# kaga_iot.net
KiCad netlist of a schematic drawn in EAGLE
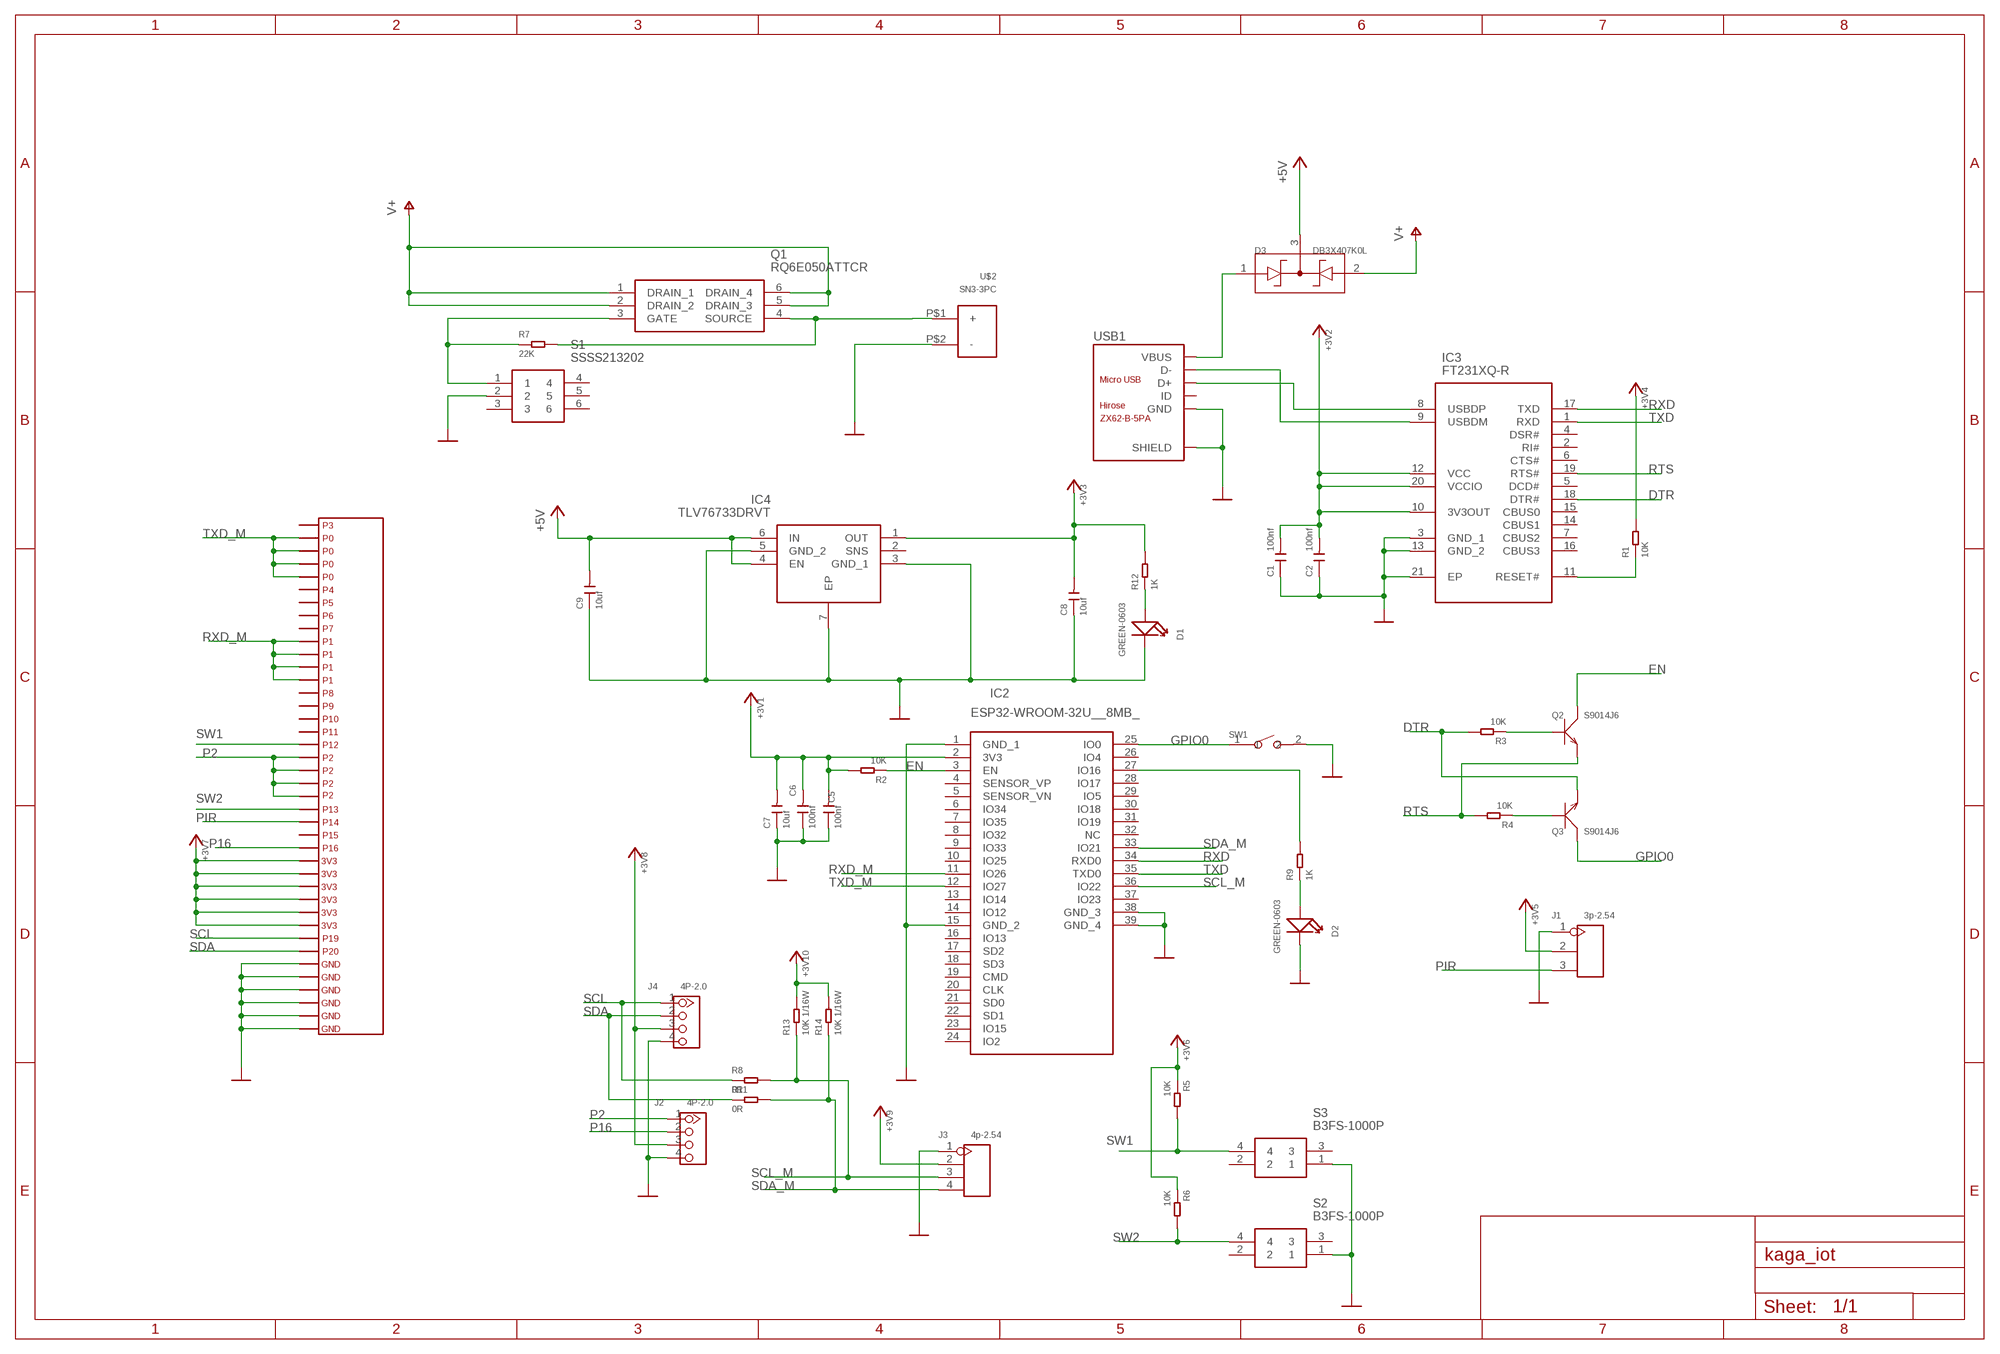
[diagram p0: schematic, sheet 1]

(export (version "E")
  (design (tool "Eeschema 10.0.6"))
  (components
    (comp (ref "C1")
      (value "100nf")
      (footprint "eagle-import:C0603")
      (fields (field (name "MPN") "CC0603KRX7R9BB104"))
      (libsource (lib "eagle-import") (part "CERAMIC-100NF-50V-10%-X7R(0603)"))
    )
    (comp (ref "C2")
      (value "100nf")
      (footprint "eagle-import:C0603")
      (fields (field (name "MPN") "CC0603KRX7R9BB104"))
      (libsource (lib "eagle-import") (part "CERAMIC-100NF-50V-10%-X7R(0603)"))
    )
    (comp (ref "C5")
      (value "100nf")
      (footprint "eagle-import:C0603")
      (fields (field (name "MPN") "CC0603KRX7R9BB104"))
      (libsource (lib "eagle-import") (part "CERAMIC-100NF-50V-10%-X7R(0603)"))
    )
    (comp (ref "C6")
      (value "100nf")
      (footprint "eagle-import:C0603")
      (fields (field (name "MPN") "CC0603KRX7R9BB104"))
      (libsource (lib "eagle-import") (part "CERAMIC-100NF-50V-10%-X7R(0603)"))
    )
    (comp (ref "C7")
      (value "10uf")
      (footprint "eagle-import:C0603")
      (fields (field (name "MPN") "CC0603KRX5R6BB106"))
      (libsource (lib "eagle-import") (part "Seeed-OPL-Capacitor_CERAMIC-10UF-10V-10%-X5R(0603)"))
    )
    (comp (ref "C8")
      (value "10uf")
      (footprint "eagle-import:C0603")
      (fields (field (name "MPN") "CC0603KRX5R6BB106"))
      (libsource (lib "eagle-import") (part "CERAMIC-10UF-10V-10%-X5R(0603)"))
    )
    (comp (ref "C9")
      (value "10uf")
      (footprint "eagle-import:C0603")
      (fields (field (name "MPN") "CC0603KRX5R6BB106"))
      (libsource (lib "eagle-import") (part "CERAMIC-10UF-10V-10%-X5R(0603)"))
    )
    (comp (ref "D1")
      (value "GREEN-0603")
      (footprint "eagle-import:LED-0603")
      (fields (field (name "MPN") "19-217-G7C-AN1P2-3T"))
      (libsource (lib "eagle-import") (part "SMD-LED-CLEAR-GREEN(0603)"))
    )
    (comp (ref "D2")
      (value "GREEN-0603")
      (footprint "eagle-import:LED-0603")
      (fields (field (name "MPN") "19-217-G7C-AN1P2-3T"))
      (libsource (lib "eagle-import") (part "SMD-LED-CLEAR-GREEN(0603)"))
    )
    (comp (ref "D3")
      (value "DB3X407K0L")
      (footprint "eagle-import:SOT-23")
      (fields (field (name "MPN") "BAT54C-215"))
      (libsource (lib "eagle-import") (part "SMD-DIODE-SCHOTTKY-30V-200MA(SOT-23)"))
    )
    (comp (ref "IC2")
      (value "ESP32-WROOM-32U__8MB_")
      (footprint "eagle-import:ESP32WROOM32U8MB")
      (fields (field (name "MANUFACTURER_PART_NUMBER") "ESP32-WROOM-32U (8MB)"))
      (libsource (lib "eagle-import") (part "ESP32-WROOM-32U__8MB_"))
    )
    (comp (ref "IC3")
      (value "FT231XQ-R")
      (footprint "eagle-import:QFN50P400X400X80-21N")
      (fields (field (name "RS_PART_NUMBER") "7570045P"))
      (libsource (lib "eagle-import") (part "FT231XQ-R"))
    )
    (comp (ref "IC4")
      (value "TLV76733DRVT")
      (footprint "eagle-import:SON65P200X200X80-7N")
      (libsource (lib "eagle-import") (part "TLV76733DRVT"))
    )
    (comp (ref "J1")
      (value "3p-2.54")
      (footprint "eagle-import:H3-2.54")
      (fields (field (name "MPN") "F185-1103A0BSYA1"))
      (libsource (lib "eagle-import") (part "DIP-BLACK-FEMALE-HEADER-VERT(3P-2.54)"))
    )
    (comp (ref "J2")
      (value "4P-2.0")
      (footprint "eagle-import:HW4-2.0")
      (libsource (lib "eagle-import") (part "GROVE-CONNECTOR-DIP(4P-2.0)"))
    )
    (comp (ref "J3")
      (value "4p-2.54")
      (footprint "eagle-import:H4-2.54")
      (fields (field (name "MPN") "F185-1104A1BSYA1"))
      (libsource (lib "eagle-import") (part "DIP-BLACK-FEMALE-HEADER-VERT(4P-2.54)"))
    )
    (comp (ref "J4")
      (value "4P-2.0")
      (footprint "eagle-import:HW4-2.0")
      (libsource (lib "eagle-import") (part "GROVE-CONNECTOR-DIP(4P-2.0)"))
    )
    (comp (ref "Q1")
      (value "RQ6E050ATTCR")
      (footprint "eagle-import:SOT95P280X100-6N")
      (fields (field (name "RS_PART_NUMBER") "1246805P"))
      (libsource (lib "eagle-import") (part "RQ6E050ATTCR"))
    )
    (comp (ref "Q2")
      (value "S9014J6")
      (footprint "eagle-import:SOT-23")
      (libsource (lib "eagle-import") (part "SMD-TRANSISTOR-NPN-50V-100MA-S9014J6(SOT-23)"))
    )
    (comp (ref "Q3")
      (value "S9014J6")
      (footprint "eagle-import:SOT-23")
      (libsource (lib "eagle-import") (part "SMD-TRANSISTOR-NPN-50V-100MA-S9014J6(SOT-23)"))
    )
    (comp (ref "R1")
      (value "10K")
      (footprint "eagle-import:R0603")
      (fields (field (name "MPN") "RC0603FR-0710KL"))
      (libsource (lib "eagle-import") (part "SMD-RES-10K-1%-1/10W(0603)"))
    )
    (comp (ref "R2")
      (value "10K")
      (footprint "eagle-import:R0603")
      (fields (field (name "MPN") "RC0603FR-0710KL"))
      (libsource (lib "eagle-import") (part "SMD-RES-10K-1%-1/10W(0603)"))
    )
    (comp (ref "R3")
      (value "10K")
      (footprint "eagle-import:R0603")
      (fields (field (name "MPN") "RC0603FR-0710KL"))
      (libsource (lib "eagle-import") (part "SMD-RES-10K-1%-1/10W(0603)"))
    )
    (comp (ref "R4")
      (value "10K")
      (footprint "eagle-import:R0603")
      (fields (field (name "MPN") "RC0603FR-0710KL"))
      (libsource (lib "eagle-import") (part "SMD-RES-10K-1%-1/10W(0603)"))
    )
    (comp (ref "R5")
      (value "10K")
      (footprint "eagle-import:R0603")
      (fields (field (name "MPN") "RC0603FR-0710KL"))
      (libsource (lib "eagle-import") (part "SMD-RES-10K-1%-1/10W(0603)"))
    )
    (comp (ref "R6")
      (value "10K")
      (footprint "eagle-import:R0603")
      (fields (field (name "MPN") "RC0603FR-0710KL"))
      (libsource (lib "eagle-import") (part "SMD-RES-10K-1%-1/10W(0603)"))
    )
    (comp (ref "R7")
      (value "22K")
      (footprint "eagle-import:R0402")
      (fields (field (name "MPN") "RC0402FR-0722KL"))
      (libsource (lib "eagle-import") (part "SMD-RES-22K-1%-1/16W(0402)"))
    )
    (comp (ref "R8")
      (value "0R")
      (footprint "eagle-import:R0402")
      (fields (field (name "MPN") "RC0402JR-070RL"))
      (libsource (lib "eagle-import") (part "SMD-RES-0R-5%-1/16W(0402)"))
    )
    (comp (ref "R9")
      (value "1K")
      (footprint "eagle-import:R0603")
      (fields (field (name "MPN") "RC0603FR-071KL"))
      (libsource (lib "eagle-import") (part "SMD-RES-1K-1%-1/10W(0603)"))
    )
    (comp (ref "R11")
      (value "0R")
      (footprint "eagle-import:R0402")
      (fields (field (name "MPN") "RC0402JR-070RL"))
      (libsource (lib "eagle-import") (part "SMD-RES-0R-5%-1/16W(0402)"))
    )
    (comp (ref "R12")
      (value "1K")
      (footprint "eagle-import:R0603")
      (fields (field (name "MPN") "RC0603FR-071KL"))
      (libsource (lib "eagle-import") (part "SMD-RES-1K-1%-1/10W(0603)"))
    )
    (comp (ref "R13")
      (value "10K 1/16W")
      (footprint "eagle-import:R0402")
      (fields (field (name "MPN") "RC0402FR-0710KL"))
      (libsource (lib "eagle-import") (part "SMD-RES-10K-1%-1/16W(0402)"))
    )
    (comp (ref "R14")
      (value "10K 1/16W")
      (footprint "eagle-import:R0402")
      (fields (field (name "MPN") "RC0402FR-0710KL"))
      (libsource (lib "eagle-import") (part "SMD-RES-10K-1%-1/16W(0402)"))
    )
    (comp (ref "S1")
      (value "SSSS213202")
      (footprint "eagle-import:SSSS213202")
      (fields (field (name "RS_PART_NUMBER") "1238917"))
      (libsource (lib "eagle-import") (part "SSSS213202"))
    )
    (comp (ref "S2")
      (value "B3FS-1000P")
      (footprint "eagle-import:B3FS-1000P")
      (fields (field (name "RS_PART_NUMBER") "6821254P"))
      (libsource (lib "eagle-import") (part "B3FS-1000P"))
    )
    (comp (ref "S3")
      (value "B3FS-1000P")
      (footprint "eagle-import:B3FS-1000P")
      (fields (field (name "RS_PART_NUMBER") "6821254P"))
      (libsource (lib "eagle-import") (part "B3FS-1000P"))
    )
    (comp (ref "SW1")
      (value "SMD-BUTTON(2P-3.0X2.5X1.2+0.4MM)-B3U-1000P-2P-SMD")
      (footprint "eagle-import:SW2-2.6-3.0X2.5X1.2+0.4MM")
      (libsource (lib "eagle-import") (part "SMD-BUTTON(2P-3.0X2.5X1.2+0.4MM)-B3U-1000P-2P-SMD"))
    )
    (comp (ref "U$1")
      (value "SMD_BBC_EDG2")
      (footprint "eagle-import:SMD_BBC_EDG2")
      (libsource (lib "eagle-import") (part "SMD_BBC_EDG2"))
    )
    (comp (ref "U$2")
      (value "SN3-3PC")
      (footprint "eagle-import:SN3-3PC")
      (libsource (lib "eagle-import") (part "SN3-3PC"))
    )
    (comp (ref "USB1")
      (value "ZX62-B-5PA")
      (footprint "eagle-import:MICRO-USB5+6P-SMD-0.65-AB")
      (libsource (lib "eagle-import") (part "MICRO-USB-SMD(ZX62-B-5PA)"))
    )
  )
  (nets
    (net (code "1") (name "+5V") (class "Default")
      (node (ref "C9") (pin "2") (pinfunction "2_2") (pintype "passive"))
      (node (ref "D3") (pin "3") (pinfunction "3_3") (pintype "bidirectional"))
      (node (ref "IC4") (pin "4") (pinfunction "EN_4") (pintype "bidirectional"))
      (node (ref "IC4") (pin "6") (pinfunction "IN_6") (pintype "bidirectional"))
    )
    (net (code "2") (name "/DTR") (class "Default")
      (node (ref "IC3") (pin "18") (pinfunction "DTR#_18") (pintype "bidirectional"))
      (node (ref "Q3") (pin "2") (pinfunction "E_2") (pintype "passive"))
      (node (ref "R3") (pin "2") (pinfunction "2_2") (pintype "passive"))
    )
    (net (code "3") (name "/EN") (class "Default")
      (node (ref "IC2") (pin "3") (pinfunction "EN_3") (pintype "bidirectional"))
      (node (ref "Q2") (pin "3") (pinfunction "C_3") (pintype "passive"))
      (node (ref "R2") (pin "1") (pinfunction "1_1") (pintype "passive"))
    )
    (net (code "4") (name "/GPIO0") (class "Default")
      (node (ref "IC2") (pin "25") (pinfunction "IO0_25") (pintype "bidirectional"))
      (node (ref "Q3") (pin "3") (pinfunction "C_3") (pintype "passive"))
      (node (ref "SW1") (pin "1") (pinfunction "1_1") (pintype "bidirectional"))
    )
    (net (code "5") (name "/P2") (class "Default")
      (node (ref "J2") (pin "1") (pinfunction "1_1") (pintype "bidirectional"))
      (node (ref "U$1") (pin "P$59") (pinfunction "P$59_P$59") (pintype "bidirectional"))
      (node (ref "U$1") (pin "P$60") (pinfunction "P$60_P$60") (pintype "bidirectional"))
      (node (ref "U$1") (pin "P$61") (pinfunction "P$61_P$61") (pintype "bidirectional"))
      (node (ref "U$1") (pin "P$62") (pinfunction "P$62_P$62") (pintype "bidirectional"))
    )
    (net (code "6") (name "/P16") (class "Default")
      (node (ref "J2") (pin "2") (pinfunction "2_2") (pintype "bidirectional"))
      (node (ref "U$1") (pin "P$55") (pinfunction "P$55_P$55") (pintype "bidirectional"))
    )
    (net (code "7") (name "/PIR") (class "Default")
      (node (ref "J1") (pin "3") (pinfunction "P$3_3") (pintype "bidirectional"))
      (node (ref "U$1") (pin "P$57") (pinfunction "P$57_P$57") (pintype "bidirectional"))
    )
    (net (code "8") (name "/RTS") (class "Default")
      (node (ref "IC3") (pin "19") (pinfunction "RTS#_19") (pintype "bidirectional"))
      (node (ref "Q2") (pin "2") (pinfunction "E_2") (pintype "passive"))
      (node (ref "R4") (pin "2") (pinfunction "2_2") (pintype "passive"))
    )
    (net (code "9") (name "/RXD") (class "Default")
      (node (ref "IC2") (pin "34") (pinfunction "RXD0_34") (pintype "bidirectional"))
      (node (ref "IC3") (pin "17") (pinfunction "TXD_17") (pintype "bidirectional"))
    )
    (net (code "10") (name "/RXD_M") (class "Default")
      (node (ref "IC2") (pin "11") (pinfunction "IO26_11") (pintype "bidirectional"))
      (node (ref "U$1") (pin "P$68") (pinfunction "P$68_P$68") (pintype "bidirectional"))
      (node (ref "U$1") (pin "P$69") (pinfunction "P$69_P$69") (pintype "bidirectional"))
      (node (ref "U$1") (pin "P$70") (pinfunction "P$70_P$70") (pintype "bidirectional"))
      (node (ref "U$1") (pin "P$71") (pinfunction "P$71_P$71") (pintype "bidirectional"))
    )
    (net (code "11") (name "/SCL") (class "Default")
      (node (ref "J4") (pin "1") (pinfunction "1_1") (pintype "bidirectional"))
      (node (ref "R8") (pin "1") (pinfunction "1_1") (pintype "passive"))
      (node (ref "U$1") (pin "P$48") (pinfunction "P$48_P$48") (pintype "bidirectional"))
    )
    (net (code "12") (name "/SCL_M") (class "Default")
      (node (ref "IC2") (pin "36") (pinfunction "IO22_36") (pintype "bidirectional"))
      (node (ref "J3") (pin "3") (pinfunction "P$3_3") (pintype "bidirectional"))
      (node (ref "R13") (pin "1") (pinfunction "1_1") (pintype "passive"))
      (node (ref "R8") (pin "2") (pinfunction "2_2") (pintype "passive"))
    )
    (net (code "13") (name "/SDA") (class "Default")
      (node (ref "J4") (pin "2") (pinfunction "2_2") (pintype "bidirectional"))
      (node (ref "R11") (pin "1") (pinfunction "1_1") (pintype "passive"))
      (node (ref "U$1") (pin "P$47") (pinfunction "P$47_P$47") (pintype "bidirectional"))
    )
    (net (code "14") (name "/SDA_M") (class "Default")
      (node (ref "IC2") (pin "33") (pinfunction "IO21_33") (pintype "bidirectional"))
      (node (ref "J3") (pin "4") (pinfunction "P$4_4") (pintype "bidirectional"))
      (node (ref "R11") (pin "2") (pinfunction "2_2") (pintype "passive"))
      (node (ref "R14") (pin "1") (pinfunction "1_1") (pintype "passive"))
    )
    (net (code "15") (name "/SW1") (class "Default")
      (node (ref "R5") (pin "2") (pinfunction "2_2") (pintype "passive"))
      (node (ref "S3") (pin "4") (pinfunction "4_4") (pintype "bidirectional"))
      (node (ref "U$1") (pin "P$63") (pinfunction "P$63_P$63") (pintype "bidirectional"))
    )
    (net (code "16") (name "/SW2") (class "Default")
      (node (ref "R6") (pin "2") (pinfunction "2_2") (pintype "passive"))
      (node (ref "S2") (pin "4") (pinfunction "4_4") (pintype "bidirectional"))
      (node (ref "U$1") (pin "P$58") (pinfunction "P$58_P$58") (pintype "bidirectional"))
    )
    (net (code "17") (name "/TXD") (class "Default")
      (node (ref "IC2") (pin "35") (pinfunction "TXD0_35") (pintype "bidirectional"))
      (node (ref "IC3") (pin "1") (pinfunction "RXD_1") (pintype "bidirectional"))
    )
    (net (code "18") (name "/TXD_M") (class "Default")
      (node (ref "IC2") (pin "12") (pinfunction "IO27_12") (pintype "bidirectional"))
      (node (ref "U$1") (pin "P$76") (pinfunction "P$76_P$76") (pintype "bidirectional"))
      (node (ref "U$1") (pin "P$77") (pinfunction "P$77_P$77") (pintype "bidirectional"))
      (node (ref "U$1") (pin "P$78") (pinfunction "P$78_P$78") (pintype "bidirectional"))
      (node (ref "U$1") (pin "P$79") (pinfunction "P$79_P$79") (pintype "bidirectional"))
    )
    (net (code "19") (name "Net-(D1-Pad+)") (class "Default")
      (node (ref "D1") (pin "+") (pinfunction "+_+") (pintype "passive"))
      (node (ref "R12") (pin "1") (pinfunction "1_1") (pintype "passive"))
    )
    (net (code "20") (name "Net-(D2-Pad+)") (class "Default")
      (node (ref "D2") (pin "+") (pinfunction "+_+") (pintype "passive"))
      (node (ref "R9") (pin "1") (pinfunction "1_1") (pintype "passive"))
    )
    (net (code "21") (name "Net-(IC2-IO16)") (class "Default")
      (node (ref "IC2") (pin "27") (pinfunction "IO16_27") (pintype "bidirectional"))
      (node (ref "R9") (pin "2") (pinfunction "2_2") (pintype "passive"))
    )
    (net (code "22") (name "Net-(IC3-RESET#)") (class "Default")
      (node (ref "IC3") (pin "11") (pinfunction "RESET#_11") (pintype "bidirectional"))
      (node (ref "R1") (pin "1") (pinfunction "1_1") (pintype "passive"))
    )
    (net (code "23") (name "Net-(IC3-USBDM)") (class "Default")
      (node (ref "IC3") (pin "9") (pinfunction "USBDM_9") (pintype "bidirectional"))
      (node (ref "USB1") (pin "2") (pinfunction "D-_2") (pintype "bidirectional"))
    )
    (net (code "24") (name "Net-(IC3-USBDP)") (class "Default")
      (node (ref "IC3") (pin "8") (pinfunction "USBDP_8") (pintype "bidirectional"))
      (node (ref "USB1") (pin "3") (pinfunction "D+_3") (pintype "bidirectional"))
    )
    (net (code "25") (name "Net-(Q1-GATE)") (class "Default")
      (node (ref "Q1") (pin "3") (pinfunction "GATE_3") (pintype "bidirectional"))
      (node (ref "R7") (pin "1") (pinfunction "1_1") (pintype "passive"))
      (node (ref "S1") (pin "1") (pinfunction "1_1") (pintype "bidirectional"))
    )
    (net (code "26") (name "Net-(Q1-SOURCE)") (class "Default")
      (node (ref "Q1") (pin "4") (pinfunction "SOURCE_4") (pintype "bidirectional"))
      (node (ref "R7") (pin "2") (pinfunction "2_2") (pintype "passive"))
      (node (ref "U$2") (pin "P$1") (pinfunction "+_P$1") (pintype "bidirectional"))
    )
    (net (code "27") (name "Net-(Q2-B)") (class "Default")
      (node (ref "Q2") (pin "1") (pinfunction "B_1") (pintype "passive"))
      (node (ref "R3") (pin "1") (pinfunction "1_1") (pintype "passive"))
    )
    (net (code "28") (name "Net-(Q3-B)") (class "Default")
      (node (ref "Q3") (pin "1") (pinfunction "B_1") (pintype "passive"))
      (node (ref "R4") (pin "1") (pinfunction "1_1") (pintype "passive"))
    )
    (net (code "29") (name "Net-(USB1-VBUS)") (class "Default")
      (node (ref "D3") (pin "1") (pinfunction "1_1") (pintype "bidirectional"))
      (node (ref "USB1") (pin "1") (pinfunction "VBUS_1") (pintype "power_in"))
    )
    (net (code "30") (name "POW_+3V3") (class "Default")
      (node (ref "C1") (pin "2") (pinfunction "2_2") (pintype "passive"))
      (node (ref "C2") (pin "2") (pinfunction "2_2") (pintype "passive"))
      (node (ref "C5") (pin "2") (pinfunction "2_2") (pintype "passive"))
      (node (ref "C6") (pin "2") (pinfunction "2_2") (pintype "passive"))
      (node (ref "C7") (pin "2") (pinfunction "2_2") (pintype "passive"))
      (node (ref "C8") (pin "2") (pinfunction "2_2") (pintype "passive"))
      (node (ref "IC2") (pin "2") (pinfunction "3V3_2") (pintype "bidirectional"))
      (node (ref "IC3") (pin "10") (pinfunction "3V3OUT_10") (pintype "bidirectional"))
      (node (ref "IC3") (pin "12") (pinfunction "VCC_12") (pintype "bidirectional"))
      (node (ref "IC3") (pin "20") (pinfunction "VCCIO_20") (pintype "bidirectional"))
      (node (ref "IC4") (pin "1") (pinfunction "OUT_1") (pintype "bidirectional"))
      (node (ref "J1") (pin "2") (pinfunction "P$2_2") (pintype "bidirectional"))
      (node (ref "J2") (pin "3") (pinfunction "3_3") (pintype "bidirectional"))
      (node (ref "J3") (pin "2") (pinfunction "P$2_2") (pintype "bidirectional"))
      (node (ref "J4") (pin "3") (pinfunction "3_3") (pintype "bidirectional"))
      (node (ref "R1") (pin "2") (pinfunction "2_2") (pintype "passive"))
      (node (ref "R12") (pin "2") (pinfunction "2_2") (pintype "passive"))
      (node (ref "R13") (pin "2") (pinfunction "2_2") (pintype "passive"))
      (node (ref "R14") (pin "2") (pinfunction "2_2") (pintype "passive"))
      (node (ref "R2") (pin "2") (pinfunction "2_2") (pintype "passive"))
      (node (ref "R5") (pin "1") (pinfunction "1_1") (pintype "passive"))
      (node (ref "R6") (pin "1") (pinfunction "1_1") (pintype "passive"))
      (node (ref "U$1") (pin "P$49") (pinfunction "P$49_P$49") (pintype "bidirectional"))
      (node (ref "U$1") (pin "P$50") (pinfunction "P$50_P$50") (pintype "bidirectional"))
      (node (ref "U$1") (pin "P$51") (pinfunction "P$51_P$51") (pintype "bidirectional"))
      (node (ref "U$1") (pin "P$52") (pinfunction "P$52_P$52") (pintype "bidirectional"))
      (node (ref "U$1") (pin "P$53") (pinfunction "P$53_P$53") (pintype "bidirectional"))
      (node (ref "U$1") (pin "P$54") (pinfunction "P$54_P$54") (pintype "bidirectional"))
    )
    (net (code "31") (name "POW_GND") (class "Default")
      (node (ref "C1") (pin "1") (pinfunction "1_1") (pintype "passive"))
      (node (ref "C2") (pin "1") (pinfunction "1_1") (pintype "passive"))
      (node (ref "C5") (pin "1") (pinfunction "1_1") (pintype "passive"))
      (node (ref "C6") (pin "1") (pinfunction "1_1") (pintype "passive"))
      (node (ref "C7") (pin "1") (pinfunction "1_1") (pintype "passive"))
      (node (ref "C8") (pin "1") (pinfunction "1_1") (pintype "passive"))
      (node (ref "C9") (pin "1") (pinfunction "1_1") (pintype "passive"))
      (node (ref "D1") (pin "-") (pinfunction "-_-") (pintype "passive"))
      (node (ref "D2") (pin "-") (pinfunction "-_-") (pintype "passive"))
      (node (ref "IC2") (pin "1") (pinfunction "GND_1_1") (pintype "bidirectional"))
      (node (ref "IC2") (pin "15") (pinfunction "GND_2_15") (pintype "bidirectional"))
      (node (ref "IC2") (pin "38") (pinfunction "GND_3_38") (pintype "bidirectional"))
      (node (ref "IC2") (pin "39") (pinfunction "GND_4_39") (pintype "bidirectional"))
      (node (ref "IC3") (pin "13") (pinfunction "GND_2_13") (pintype "bidirectional"))
      (node (ref "IC3") (pin "21") (pinfunction "EP_21") (pintype "bidirectional"))
      (node (ref "IC3") (pin "3") (pinfunction "GND_1_3") (pintype "bidirectional"))
      (node (ref "IC4") (pin "3") (pinfunction "GND_1_3") (pintype "bidirectional"))
      (node (ref "IC4") (pin "5") (pinfunction "GND_2_5") (pintype "bidirectional"))
      (node (ref "IC4") (pin "7") (pinfunction "EP_7") (pintype "bidirectional"))
      (node (ref "J1") (pin "1") (pinfunction "P$1_1") (pintype "bidirectional"))
      (node (ref "J2") (pin "4") (pinfunction "4_4") (pintype "bidirectional"))
      (node (ref "J3") (pin "1") (pinfunction "P$1_1") (pintype "bidirectional"))
      (node (ref "J4") (pin "4") (pinfunction "4_4") (pintype "bidirectional"))
      (node (ref "S1") (pin "2") (pinfunction "2_2") (pintype "bidirectional"))
      (node (ref "S2") (pin "1") (pinfunction "1_1") (pintype "bidirectional"))
      (node (ref "S3") (pin "1") (pinfunction "1_1") (pintype "bidirectional"))
      (node (ref "SW1") (pin "2") (pinfunction "2_2") (pintype "bidirectional"))
      (node (ref "U$1") (pin "P$41") (pinfunction "P$41_P$41") (pintype "bidirectional"))
      (node (ref "U$1") (pin "P$42") (pinfunction "P$42_P$42") (pintype "bidirectional"))
      (node (ref "U$1") (pin "P$43") (pinfunction "P$43_P$43") (pintype "bidirectional"))
      (node (ref "U$1") (pin "P$44") (pinfunction "P$44_P$44") (pintype "bidirectional"))
      (node (ref "U$1") (pin "P$45") (pinfunction "P$45_P$45") (pintype "bidirectional"))
      (node (ref "U$1") (pin "P$46") (pinfunction "P$46_P$46") (pintype "bidirectional"))
      (node (ref "U$2") (pin "P$2") (pinfunction "-_P$2") (pintype "bidirectional"))
      (node (ref "USB1") (pin "5") (pinfunction "GND_5") (pintype "power_in"))
      (node (ref "USB1") (pin "P1") (pinfunction "SHIELD_P1") (pintype "power_in"))
      (node (ref "USB1") (pin "P2") (pinfunction "SHIELD_P2") (pintype "power_in"))
      (node (ref "USB1") (pin "P3") (pinfunction "SHIELD_P3") (pintype "power_in"))
      (node (ref "USB1") (pin "P4") (pinfunction "SHIELD_P4") (pintype "power_in"))
      (node (ref "USB1") (pin "P5") (pinfunction "SHIELD_P5") (pintype "power_in"))
      (node (ref "USB1") (pin "P6") (pinfunction "SHIELD_P6") (pintype "power_in"))
    )
    (net (code "32") (name "V+") (class "Default")
      (node (ref "D3") (pin "2") (pinfunction "2_2") (pintype "bidirectional"))
      (node (ref "Q1") (pin "1") (pinfunction "DRAIN_1_1") (pintype "bidirectional"))
      (node (ref "Q1") (pin "2") (pinfunction "DRAIN_2_2") (pintype "bidirectional"))
      (node (ref "Q1") (pin "5") (pinfunction "DRAIN_3_5") (pintype "bidirectional"))
      (node (ref "Q1") (pin "6") (pinfunction "DRAIN_4_6") (pintype "bidirectional"))
    )
    (net (code "33") (name "unconnected-(IC2-CLK-Pad20)") (class "Default")
      (node (ref "IC2") (pin "20") (pinfunction "CLK_20") (pintype "bidirectional"))
    )
    (net (code "34") (name "unconnected-(IC2-CMD-Pad19)") (class "Default")
      (node (ref "IC2") (pin "19") (pinfunction "CMD_19") (pintype "bidirectional"))
    )
    (net (code "35") (name "unconnected-(IC2-IO2-Pad24)") (class "Default")
      (node (ref "IC2") (pin "24") (pinfunction "IO2_24") (pintype "bidirectional"))
    )
    (net (code "36") (name "unconnected-(IC2-IO4-Pad26)") (class "Default")
      (node (ref "IC2") (pin "26") (pinfunction "IO4_26") (pintype "bidirectional"))
    )
    (net (code "37") (name "unconnected-(IC2-IO5-Pad29)") (class "Default")
      (node (ref "IC2") (pin "29") (pinfunction "IO5_29") (pintype "bidirectional"))
    )
    (net (code "38") (name "unconnected-(IC2-IO12-Pad14)") (class "Default")
      (node (ref "IC2") (pin "14") (pinfunction "IO12_14") (pintype "bidirectional"))
    )
    (net (code "39") (name "unconnected-(IC2-IO13-Pad16)") (class "Default")
      (node (ref "IC2") (pin "16") (pinfunction "IO13_16") (pintype "bidirectional"))
    )
    (net (code "40") (name "unconnected-(IC2-IO14-Pad13)") (class "Default")
      (node (ref "IC2") (pin "13") (pinfunction "IO14_13") (pintype "bidirectional"))
    )
    (net (code "41") (name "unconnected-(IC2-IO15-Pad23)") (class "Default")
      (node (ref "IC2") (pin "23") (pinfunction "IO15_23") (pintype "bidirectional"))
    )
    (net (code "42") (name "unconnected-(IC2-IO17-Pad28)") (class "Default")
      (node (ref "IC2") (pin "28") (pinfunction "IO17_28") (pintype "bidirectional"))
    )
    (net (code "43") (name "unconnected-(IC2-IO18-Pad30)") (class "Default")
      (node (ref "IC2") (pin "30") (pinfunction "IO18_30") (pintype "bidirectional"))
    )
    (net (code "44") (name "unconnected-(IC2-IO19-Pad31)") (class "Default")
      (node (ref "IC2") (pin "31") (pinfunction "IO19_31") (pintype "bidirectional"))
    )
    (net (code "45") (name "unconnected-(IC2-IO23-Pad37)") (class "Default")
      (node (ref "IC2") (pin "37") (pinfunction "IO23_37") (pintype "bidirectional"))
    )
    (net (code "46") (name "unconnected-(IC2-IO25-Pad10)") (class "Default")
      (node (ref "IC2") (pin "10") (pinfunction "IO25_10") (pintype "bidirectional"))
    )
    (net (code "47") (name "unconnected-(IC2-IO32-Pad8)") (class "Default")
      (node (ref "IC2") (pin "8") (pinfunction "IO32_8") (pintype "bidirectional"))
    )
    (net (code "48") (name "unconnected-(IC2-IO33-Pad9)") (class "Default")
      (node (ref "IC2") (pin "9") (pinfunction "IO33_9") (pintype "bidirectional"))
    )
    (net (code "49") (name "unconnected-(IC2-IO34-Pad6)") (class "Default")
      (node (ref "IC2") (pin "6") (pinfunction "IO34_6") (pintype "bidirectional"))
    )
    (net (code "50") (name "unconnected-(IC2-IO35-Pad7)") (class "Default")
      (node (ref "IC2") (pin "7") (pinfunction "IO35_7") (pintype "bidirectional"))
    )
    (net (code "51") (name "unconnected-(IC2-NC-Pad32)") (class "Default")
      (node (ref "IC2") (pin "32") (pinfunction "NC_32") (pintype "no_connect"))
    )
    (net (code "52") (name "unconnected-(IC2-SD0-Pad21)") (class "Default")
      (node (ref "IC2") (pin "21") (pinfunction "SD0_21") (pintype "bidirectional"))
    )
    (net (code "53") (name "unconnected-(IC2-SD1-Pad22)") (class "Default")
      (node (ref "IC2") (pin "22") (pinfunction "SD1_22") (pintype "bidirectional"))
    )
    (net (code "54") (name "unconnected-(IC2-SD2-Pad17)") (class "Default")
      (node (ref "IC2") (pin "17") (pinfunction "SD2_17") (pintype "bidirectional"))
    )
    (net (code "55") (name "unconnected-(IC2-SD3-Pad18)") (class "Default")
      (node (ref "IC2") (pin "18") (pinfunction "SD3_18") (pintype "bidirectional"))
    )
    (net (code "56") (name "unconnected-(IC2-SENSOR_VN-Pad5)") (class "Default")
      (node (ref "IC2") (pin "5") (pinfunction "SENSOR_VN_5") (pintype "bidirectional"))
    )
    (net (code "57") (name "unconnected-(IC2-SENSOR_VP-Pad4)") (class "Default")
      (node (ref "IC2") (pin "4") (pinfunction "SENSOR_VP_4") (pintype "bidirectional"))
    )
    (net (code "58") (name "unconnected-(IC3-CBUS0-Pad15)") (class "Default")
      (node (ref "IC3") (pin "15") (pinfunction "CBUS0_15") (pintype "bidirectional"))
    )
    (net (code "59") (name "unconnected-(IC3-CBUS1-Pad14)") (class "Default")
      (node (ref "IC3") (pin "14") (pinfunction "CBUS1_14") (pintype "bidirectional"))
    )
    (net (code "60") (name "unconnected-(IC3-CBUS2-Pad7)") (class "Default")
      (node (ref "IC3") (pin "7") (pinfunction "CBUS2_7") (pintype "bidirectional"))
    )
    (net (code "61") (name "unconnected-(IC3-CBUS3-Pad16)") (class "Default")
      (node (ref "IC3") (pin "16") (pinfunction "CBUS3_16") (pintype "bidirectional"))
    )
    (net (code "62") (name "unconnected-(IC3-CTS#-Pad6)") (class "Default")
      (node (ref "IC3") (pin "6") (pinfunction "CTS#_6") (pintype "bidirectional"))
    )
    (net (code "63") (name "unconnected-(IC3-DCD#-Pad5)") (class "Default")
      (node (ref "IC3") (pin "5") (pinfunction "DCD#_5") (pintype "bidirectional"))
    )
    (net (code "64") (name "unconnected-(IC3-DSR#-Pad4)") (class "Default")
      (node (ref "IC3") (pin "4") (pinfunction "DSR#_4") (pintype "bidirectional"))
    )
    (net (code "65") (name "unconnected-(IC3-RI#-Pad2)") (class "Default")
      (node (ref "IC3") (pin "2") (pinfunction "RI#_2") (pintype "bidirectional"))
    )
    (net (code "66") (name "unconnected-(IC4-SNS-Pad2)") (class "Default")
      (node (ref "IC4") (pin "2") (pinfunction "SNS_2") (pintype "bidirectional"))
    )
    (net (code "67") (name "unconnected-(S1-Pad3)") (class "Default")
      (node (ref "S1") (pin "3") (pinfunction "3_3") (pintype "bidirectional"))
    )
    (net (code "68") (name "unconnected-(S1-Pad4)") (class "Default")
      (node (ref "S1") (pin "4") (pinfunction "4_4") (pintype "bidirectional"))
    )
    (net (code "69") (name "unconnected-(S1-Pad5)") (class "Default")
      (node (ref "S1") (pin "5") (pinfunction "5_5") (pintype "bidirectional"))
    )
    (net (code "70") (name "unconnected-(S1-Pad6)") (class "Default")
      (node (ref "S1") (pin "6") (pinfunction "6_6") (pintype "bidirectional"))
    )
    (net (code "71") (name "unconnected-(S2-Pad2)") (class "Default")
      (node (ref "S2") (pin "2") (pinfunction "2_2") (pintype "bidirectional"))
    )
    (net (code "72") (name "unconnected-(S2-Pad3)") (class "Default")
      (node (ref "S2") (pin "3") (pinfunction "3_3") (pintype "bidirectional"))
    )
    (net (code "73") (name "unconnected-(S3-Pad2)") (class "Default")
      (node (ref "S3") (pin "2") (pinfunction "2_2") (pintype "bidirectional"))
    )
    (net (code "74") (name "unconnected-(S3-Pad3)") (class "Default")
      (node (ref "S3") (pin "3") (pinfunction "3_3") (pintype "bidirectional"))
    )
    (net (code "75") (name "unconnected-(U$1-PadP$56)") (class "Default")
      (node (ref "U$1") (pin "P$56") (pinfunction "P$56_P$56") (pintype "bidirectional"))
    )
    (net (code "76") (name "unconnected-(U$1-PadP$64)") (class "Default")
      (node (ref "U$1") (pin "P$64") (pinfunction "P$64_P$64") (pintype "bidirectional"))
    )
    (net (code "77") (name "unconnected-(U$1-PadP$65)") (class "Default")
      (node (ref "U$1") (pin "P$65") (pinfunction "P$65_P$65") (pintype "bidirectional"))
    )
    (net (code "78") (name "unconnected-(U$1-PadP$66)") (class "Default")
      (node (ref "U$1") (pin "P$66") (pinfunction "P$66_P$66") (pintype "bidirectional"))
    )
    (net (code "79") (name "unconnected-(U$1-PadP$67)") (class "Default")
      (node (ref "U$1") (pin "P$67") (pinfunction "P$67_P$67") (pintype "bidirectional"))
    )
    (net (code "80") (name "unconnected-(U$1-PadP$72)") (class "Default")
      (node (ref "U$1") (pin "P$72") (pinfunction "P$72_P$72") (pintype "bidirectional"))
    )
    (net (code "81") (name "unconnected-(U$1-PadP$73)") (class "Default")
      (node (ref "U$1") (pin "P$73") (pinfunction "P$73_P$73") (pintype "bidirectional"))
    )
    (net (code "82") (name "unconnected-(U$1-PadP$74)") (class "Default")
      (node (ref "U$1") (pin "P$74") (pinfunction "P$74_P$74") (pintype "bidirectional"))
    )
    (net (code "83") (name "unconnected-(U$1-PadP$75)") (class "Default")
      (node (ref "U$1") (pin "P$75") (pinfunction "P$75_P$75") (pintype "bidirectional"))
    )
    (net (code "84") (name "unconnected-(U$1-PadP$80)") (class "Default")
      (node (ref "U$1") (pin "P$80") (pinfunction "P$80_P$80") (pintype "bidirectional"))
    )
    (net (code "85") (name "unconnected-(USB1-ID-Pad4)") (class "Default")
      (node (ref "USB1") (pin "4") (pinfunction "ID_4") (pintype "bidirectional"))
    )
  )
)
